# WS2811-40mm_2024-06-16.net
KiCad netlist of a schematic drawn in EasyEDA Pro
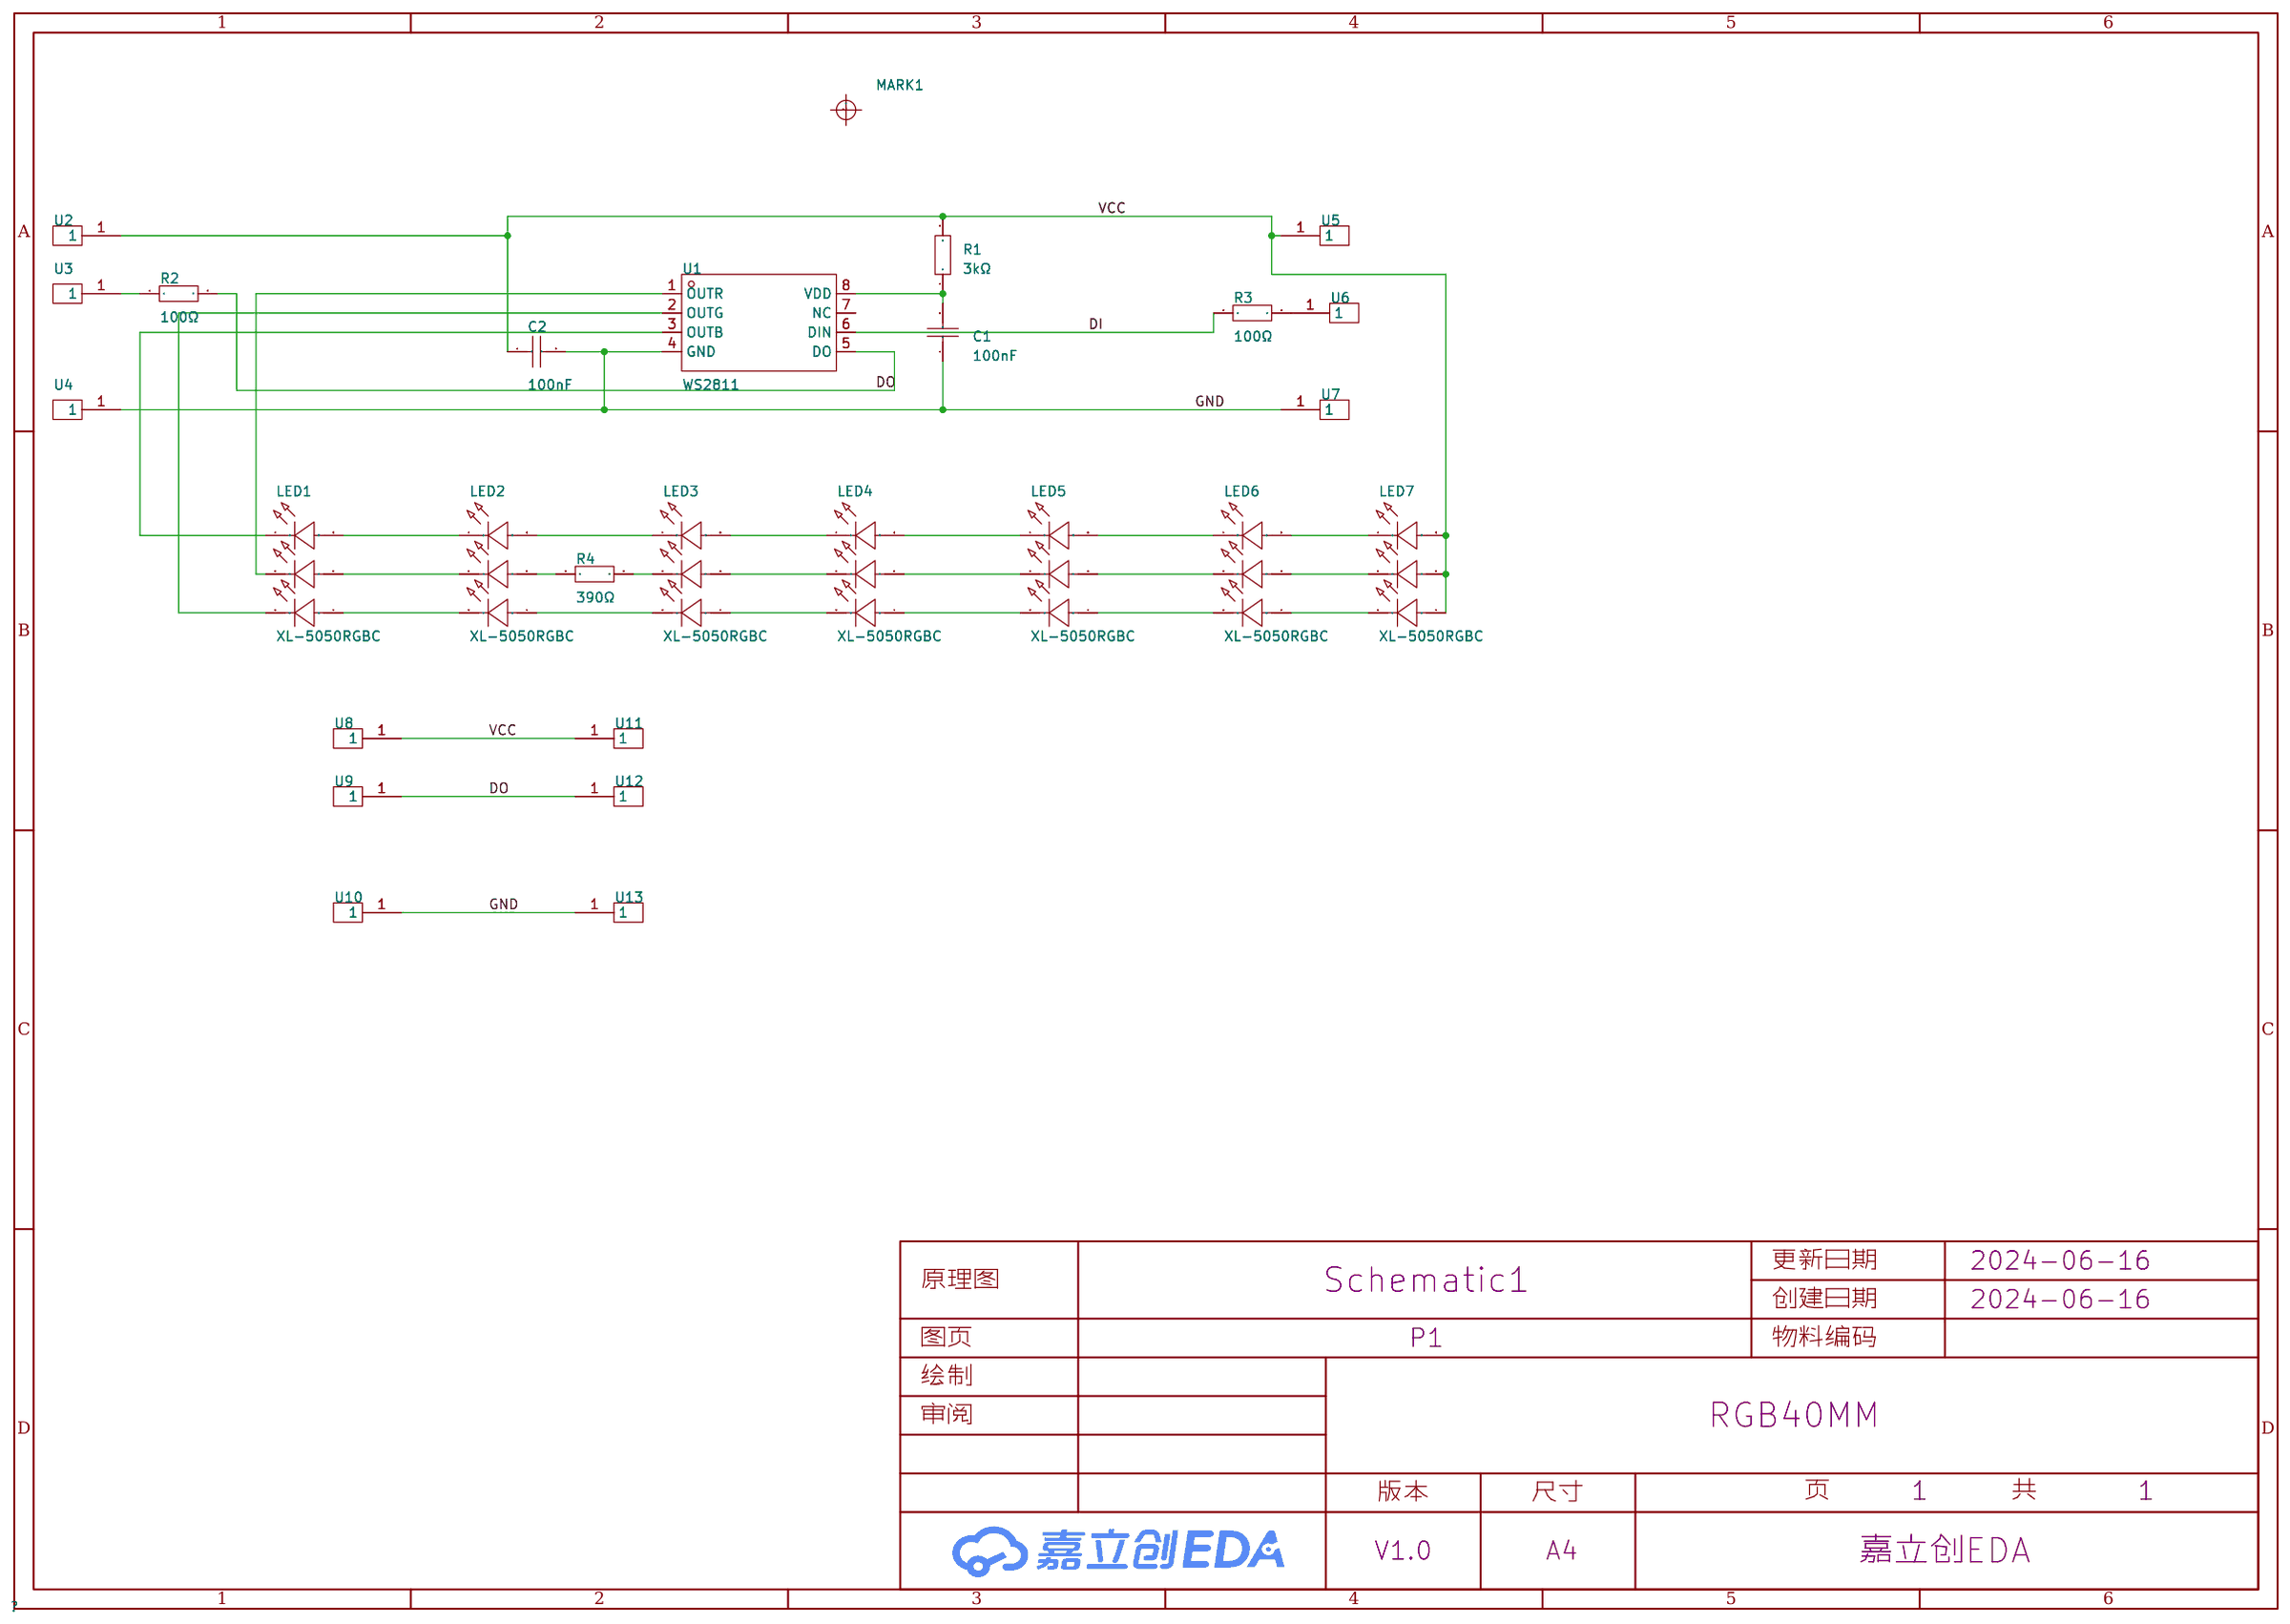
[diagram p0: schematic sheet]

(export (version "E")
  (design (tool "Eeschema 10.0.6"))
  (components
    (comp (ref "C1")
      (value "100nF")
      (footprint "easyedapro:C0805")
      (description "容值:100nF;精度:±10%;额定电压:50V;材质(温度系数):X7R;")
      (fields
        (field (name "Manufacturer Part") "CC0805KRX7R9BB104")
        (field (name "Manufacturer") "YAGEO(国巨)")
      )
      (libsource (lib "easyedapro") (part "CC0805KRX7R9BB104"))
    )
    (comp (ref "C2")
      (value "100nF")
      (footprint "easyedapro:C0805")
      (description "容值:100nF;精度:±10%;额定电压:50V;材质(温度系数):X7R;")
      (fields
        (field (name "Manufacturer Part") "CC0805KRX7R9BB104")
        (field (name "Manufacturer") "YAGEO(国巨)")
      )
      (libsource (lib "easyedapro") (part "CC0805KRX7R9BB104"))
    )
    (comp (ref "LED1")
      (value "XL-5050RGBC")
      (footprint "easyedapro:LED-ARRAY-SMD_6P-L5.0-W5.0-TL-RD_3")
      (fields (field (name "Manufacturer") "XINGLIGHT(成兴光)"))
      (libsource (lib "easyedapro") (part "XL-5050RGBC"))
    )
    (comp (ref "LED2")
      (value "XL-5050RGBC")
      (footprint "easyedapro:LED-ARRAY-SMD_6P-L5.0-W5.0-TL-RD_3")
      (fields (field (name "Manufacturer") "XINGLIGHT(成兴光)"))
      (libsource (lib "easyedapro") (part "XL-5050RGBC"))
    )
    (comp (ref "LED3")
      (value "XL-5050RGBC")
      (footprint "easyedapro:LED-ARRAY-SMD_6P-L5.0-W5.0-TL-RD_3")
      (fields (field (name "Manufacturer") "XINGLIGHT(成兴光)"))
      (libsource (lib "easyedapro") (part "XL-5050RGBC"))
    )
    (comp (ref "LED4")
      (value "XL-5050RGBC")
      (footprint "easyedapro:LED-ARRAY-SMD_6P-L5.0-W5.0-TL-RD_3")
      (fields (field (name "Manufacturer") "XINGLIGHT(成兴光)"))
      (libsource (lib "easyedapro") (part "XL-5050RGBC"))
    )
    (comp (ref "LED5")
      (value "XL-5050RGBC")
      (footprint "easyedapro:LED-ARRAY-SMD_6P-L5.0-W5.0-TL-RD_3")
      (fields (field (name "Manufacturer") "XINGLIGHT(成兴光)"))
      (libsource (lib "easyedapro") (part "XL-5050RGBC"))
    )
    (comp (ref "LED6")
      (value "XL-5050RGBC")
      (footprint "easyedapro:LED-ARRAY-SMD_6P-L5.0-W5.0-TL-RD_3")
      (fields (field (name "Manufacturer") "XINGLIGHT(成兴光)"))
      (libsource (lib "easyedapro") (part "XL-5050RGBC"))
    )
    (comp (ref "LED7")
      (value "XL-5050RGBC")
      (footprint "easyedapro:LED-ARRAY-SMD_6P-L5.0-W5.0-TL-RD_3")
      (fields (field (name "Manufacturer") "XINGLIGHT(成兴光)"))
      (libsource (lib "easyedapro") (part "XL-5050RGBC"))
    )
    (comp (ref "MARK1")
      (value "~")
      (footprint "easyedapro:Mark-Point-1mm")
      (description "Mark点")
      (libsource (lib "easyedapro") (part "Mark-Point"))
    )
    (comp (ref "R1")
      (value "3kΩ")
      (footprint "easyedapro:R1206")
      (description "电阻类型:厚膜电阻;阻值:3kΩ;精度:±1%;功率:250mW;最大工作电压:200V;温度系数:±100ppm/°C;")
      (fields
        (field (name "Manufacturer Part") "1206W4F3001T5E")
        (field (name "Manufacturer") "UNI-ROYAL(厚声)")
      )
      (libsource (lib "easyedapro") (part "1206W4F3001T5E"))
    )
    (comp (ref "R2")
      (value "100Ω")
      (footprint "easyedapro:R1206")
      (description "电阻类型:厚膜电阻;阻值:100Ω;精度:±5%;功率:250mW;最大工作电压:200V;温度系数:±100ppm/°C;")
      (fields (field (name "Manufacturer Part") "RC1206JR-07100RL") (field (name "Manufacturer") "YAGEO(国巨)"))
      (libsource (lib "easyedapro") (part "RC1206JR-07100RL"))
    )
    (comp (ref "R3")
      (value "100Ω")
      (footprint "easyedapro:R1206")
      (description "电阻类型:厚膜电阻;阻值:100Ω;精度:±5%;功率:250mW;最大工作电压:200V;温度系数:±100ppm/°C;")
      (fields (field (name "Manufacturer Part") "RC1206JR-07100RL") (field (name "Manufacturer") "YAGEO(国巨)"))
      (libsource (lib "easyedapro") (part "RC1206JR-07100RL"))
    )
    (comp (ref "R4")
      (value "390Ω")
      (footprint "easyedapro:R1206")
      (description "电阻类型:厚膜电阻;阻值:390Ω;精度:±5%;功率:250mW;最大工作电压:200V;温度系数:±100ppm/°C;")
      (fields
        (field (name "Manufacturer Part") "1206W4J0391T5E")
        (field (name "Manufacturer") "UNI-ROYAL(厚声)")
      )
      (libsource (lib "easyedapro") (part "1206W4J0391T5E"))
    )
    (comp (ref "U1")
      (value "WS2811")
      (footprint "easyedapro:SOP-8_L4.9-W3.9-P1.27-LS6.0-BL")
      (description "类型:-;输入电压:-;开关频率:-;通道数:-;输出电压:-;输出电流:-;调光:-;拓扑结构:-;")
      (fields (field (name "Manufacturer") "worldsemi"))
      (libsource (lib "easyedapro") (part "WS2811"))
    )
    (comp (ref "U2")
      (value "~")
      (footprint "easyedapro:1.7X9")
      (libsource (lib "easyedapro") (part "1P1.7X9.5"))
    )
    (comp (ref "U3")
      (value "~")
      (footprint "easyedapro:1.7X9")
      (libsource (lib "easyedapro") (part "1P1.7X9.5"))
    )
    (comp (ref "U4")
      (value "~")
      (footprint "easyedapro:1.7X9")
      (libsource (lib "easyedapro") (part "1P1.7X9.5"))
    )
    (comp (ref "U5")
      (value "~")
      (footprint "easyedapro:1.7X9")
      (libsource (lib "easyedapro") (part "1P1.7X9.5"))
    )
    (comp (ref "U6")
      (value "~")
      (footprint "easyedapro:1.7X9")
      (libsource (lib "easyedapro") (part "1P1.7X9.5"))
    )
    (comp (ref "U7")
      (value "~")
      (footprint "easyedapro:1.7X9")
      (libsource (lib "easyedapro") (part "1P1.7X9.5"))
    )
    (comp (ref "U8")
      (value "~")
      (footprint "easyedapro:1.7X9")
      (libsource (lib "easyedapro") (part "1P1.7X9.5"))
    )
    (comp (ref "U9")
      (value "~")
      (footprint "easyedapro:1.7X9")
      (libsource (lib "easyedapro") (part "1P1.7X9.5"))
    )
    (comp (ref "U10")
      (value "~")
      (footprint "easyedapro:1.7X9")
      (libsource (lib "easyedapro") (part "1P1.7X9.5"))
    )
    (comp (ref "U11")
      (value "~")
      (footprint "easyedapro:1.7X9")
      (libsource (lib "easyedapro") (part "1P1.7X9.5"))
    )
    (comp (ref "U12")
      (value "~")
      (footprint "easyedapro:1.7X9")
      (libsource (lib "easyedapro") (part "1P1.7X9.5"))
    )
    (comp (ref "U13")
      (value "~")
      (footprint "easyedapro:1.7X9")
      (libsource (lib "easyedapro") (part "1P1.7X9.5"))
    )
  )
  (nets
    (net (code "1") (name "/DI") (class "Default")
      (node (ref "R3") (pin "1") (pinfunction "1_1") (pintype "input"))
      (node (ref "U1") (pin "6") (pinfunction "DIN_6") (pintype "unspecified"))
    )
    (net (code "2") (name "/DO") (class "Default")
      (node (ref "R2") (pin "2") (pinfunction "2_2") (pintype "input"))
      (node (ref "U1") (pin "5") (pinfunction "DO_5") (pintype "unspecified"))
      (node (ref "U12") (pin "1") (pinfunction "1_1") (pintype "input"))
      (node (ref "U9") (pin "1") (pinfunction "1_1") (pintype "input"))
    )
    (net (code "3") (name "/GND") (class "Default")
      (node (ref "C1") (pin "1") (pinfunction "1_1") (pintype "input"))
      (node (ref "C2") (pin "2") (pinfunction "2_2") (pintype "input"))
      (node (ref "U1") (pin "4") (pinfunction "GND_4") (pintype "unspecified"))
      (node (ref "U10") (pin "1") (pinfunction "1_1") (pintype "input"))
      (node (ref "U13") (pin "1") (pinfunction "1_1") (pintype "input"))
      (node (ref "U4") (pin "1") (pinfunction "1_1") (pintype "input"))
      (node (ref "U7") (pin "1") (pinfunction "1_1") (pintype "input"))
    )
    (net (code "4") (name "/VCC") (class "Default")
      (node (ref "C2") (pin "1") (pinfunction "1_1") (pintype "input"))
      (node (ref "LED7") (pin "4") (pinfunction "G+_4") (pintype "unspecified"))
      (node (ref "LED7") (pin "5") (pinfunction "R+_5") (pintype "unspecified"))
      (node (ref "LED7") (pin "6") (pinfunction "B+_6") (pintype "unspecified"))
      (node (ref "R1") (pin "2") (pinfunction "2_2") (pintype "input"))
      (node (ref "U11") (pin "1") (pinfunction "1_1") (pintype "input"))
      (node (ref "U2") (pin "1") (pinfunction "1_1") (pintype "input"))
      (node (ref "U5") (pin "1") (pinfunction "1_1") (pintype "input"))
      (node (ref "U8") (pin "1") (pinfunction "1_1") (pintype "input"))
    )
    (net (code "5") (name "Net-(LED1-B+)") (class "Default")
      (node (ref "LED1") (pin "6") (pinfunction "B+_6") (pintype "unspecified"))
      (node (ref "LED2") (pin "1") (pinfunction "B-_1") (pintype "unspecified"))
    )
    (net (code "6") (name "Net-(LED1-B-)") (class "Default")
      (node (ref "LED1") (pin "1") (pinfunction "B-_1") (pintype "unspecified"))
      (node (ref "U1") (pin "3") (pinfunction "OUTB_3") (pintype "unspecified"))
    )
    (net (code "7") (name "Net-(LED1-G+)") (class "Default")
      (node (ref "LED1") (pin "4") (pinfunction "G+_4") (pintype "unspecified"))
      (node (ref "LED2") (pin "3") (pinfunction "G-_3") (pintype "unspecified"))
    )
    (net (code "8") (name "Net-(LED1-G-)") (class "Default")
      (node (ref "LED1") (pin "3") (pinfunction "G-_3") (pintype "unspecified"))
      (node (ref "U1") (pin "2") (pinfunction "OUTG_2") (pintype "unspecified"))
    )
    (net (code "9") (name "Net-(LED1-R+)") (class "Default")
      (node (ref "LED1") (pin "5") (pinfunction "R+_5") (pintype "unspecified"))
      (node (ref "LED2") (pin "2") (pinfunction "R-_2") (pintype "unspecified"))
    )
    (net (code "10") (name "Net-(LED1-R-)") (class "Default")
      (node (ref "LED1") (pin "2") (pinfunction "R-_2") (pintype "unspecified"))
      (node (ref "U1") (pin "1") (pinfunction "OUTR_1") (pintype "unspecified"))
    )
    (net (code "11") (name "Net-(LED2-B+)") (class "Default")
      (node (ref "LED2") (pin "6") (pinfunction "B+_6") (pintype "unspecified"))
      (node (ref "LED3") (pin "1") (pinfunction "B-_1") (pintype "unspecified"))
    )
    (net (code "12") (name "Net-(LED2-G+)") (class "Default")
      (node (ref "LED2") (pin "4") (pinfunction "G+_4") (pintype "unspecified"))
      (node (ref "LED3") (pin "3") (pinfunction "G-_3") (pintype "unspecified"))
    )
    (net (code "13") (name "Net-(LED2-R+)") (class "Default")
      (node (ref "LED2") (pin "5") (pinfunction "R+_5") (pintype "unspecified"))
      (node (ref "R4") (pin "1") (pinfunction "1_1") (pintype "input"))
    )
    (net (code "14") (name "Net-(LED3-B+)") (class "Default")
      (node (ref "LED3") (pin "6") (pinfunction "B+_6") (pintype "unspecified"))
      (node (ref "LED4") (pin "1") (pinfunction "B-_1") (pintype "unspecified"))
    )
    (net (code "15") (name "Net-(LED3-G+)") (class "Default")
      (node (ref "LED3") (pin "4") (pinfunction "G+_4") (pintype "unspecified"))
      (node (ref "LED4") (pin "3") (pinfunction "G-_3") (pintype "unspecified"))
    )
    (net (code "16") (name "Net-(LED3-R+)") (class "Default")
      (node (ref "LED3") (pin "5") (pinfunction "R+_5") (pintype "unspecified"))
      (node (ref "LED4") (pin "2") (pinfunction "R-_2") (pintype "unspecified"))
    )
    (net (code "17") (name "Net-(LED3-R-)") (class "Default")
      (node (ref "LED3") (pin "2") (pinfunction "R-_2") (pintype "unspecified"))
      (node (ref "R4") (pin "2") (pinfunction "2_2") (pintype "input"))
    )
    (net (code "18") (name "Net-(LED4-B+)") (class "Default")
      (node (ref "LED4") (pin "6") (pinfunction "B+_6") (pintype "unspecified"))
      (node (ref "LED5") (pin "1") (pinfunction "B-_1") (pintype "unspecified"))
    )
    (net (code "19") (name "Net-(LED4-G+)") (class "Default")
      (node (ref "LED4") (pin "4") (pinfunction "G+_4") (pintype "unspecified"))
      (node (ref "LED5") (pin "3") (pinfunction "G-_3") (pintype "unspecified"))
    )
    (net (code "20") (name "Net-(LED4-R+)") (class "Default")
      (node (ref "LED4") (pin "5") (pinfunction "R+_5") (pintype "unspecified"))
      (node (ref "LED5") (pin "2") (pinfunction "R-_2") (pintype "unspecified"))
    )
    (net (code "21") (name "Net-(LED5-B+)") (class "Default")
      (node (ref "LED5") (pin "6") (pinfunction "B+_6") (pintype "unspecified"))
      (node (ref "LED6") (pin "1") (pinfunction "B-_1") (pintype "unspecified"))
    )
    (net (code "22") (name "Net-(LED5-G+)") (class "Default")
      (node (ref "LED5") (pin "4") (pinfunction "G+_4") (pintype "unspecified"))
      (node (ref "LED6") (pin "3") (pinfunction "G-_3") (pintype "unspecified"))
    )
    (net (code "23") (name "Net-(LED5-R+)") (class "Default")
      (node (ref "LED5") (pin "5") (pinfunction "R+_5") (pintype "unspecified"))
      (node (ref "LED6") (pin "2") (pinfunction "R-_2") (pintype "unspecified"))
    )
    (net (code "24") (name "Net-(LED6-B+)") (class "Default")
      (node (ref "LED6") (pin "6") (pinfunction "B+_6") (pintype "unspecified"))
      (node (ref "LED7") (pin "1") (pinfunction "B-_1") (pintype "unspecified"))
    )
    (net (code "25") (name "Net-(LED6-G+)") (class "Default")
      (node (ref "LED6") (pin "4") (pinfunction "G+_4") (pintype "unspecified"))
      (node (ref "LED7") (pin "3") (pinfunction "G-_3") (pintype "unspecified"))
    )
    (net (code "26") (name "Net-(LED6-R+)") (class "Default")
      (node (ref "LED6") (pin "5") (pinfunction "R+_5") (pintype "unspecified"))
      (node (ref "LED7") (pin "2") (pinfunction "R-_2") (pintype "unspecified"))
    )
    (net (code "27") (name "Net-(R2-Pad1)") (class "Default")
      (node (ref "R2") (pin "1") (pinfunction "1_1") (pintype "input"))
      (node (ref "U3") (pin "1") (pinfunction "1_1") (pintype "input"))
    )
    (net (code "28") (name "Net-(R3-Pad2)") (class "Default")
      (node (ref "R3") (pin "2") (pinfunction "2_2") (pintype "input"))
      (node (ref "U6") (pin "1") (pinfunction "1_1") (pintype "input"))
    )
    (net (code "29") (name "Net-(U1-VDD)") (class "Default")
      (node (ref "C1") (pin "2") (pinfunction "2_2") (pintype "input"))
      (node (ref "R1") (pin "1") (pinfunction "1_1") (pintype "input"))
      (node (ref "U1") (pin "8") (pinfunction "VDD_8") (pintype "unspecified"))
    )
    (net (code "30") (name "unconnected-(MARK1-Pad1)") (class "Default")
      (node (ref "MARK1") (pin "1") (pinfunction "1_1") (pintype "input"))
    )
    (net (code "31") (name "unconnected-(U1-NC-Pad7)") (class "Default")
      (node (ref "U1") (pin "7") (pinfunction "NC_7") (pintype "unspecified"))
    )
  )
)
